# thermokoppel.net
KiCad netlist of a schematic drawn in Altium Designer
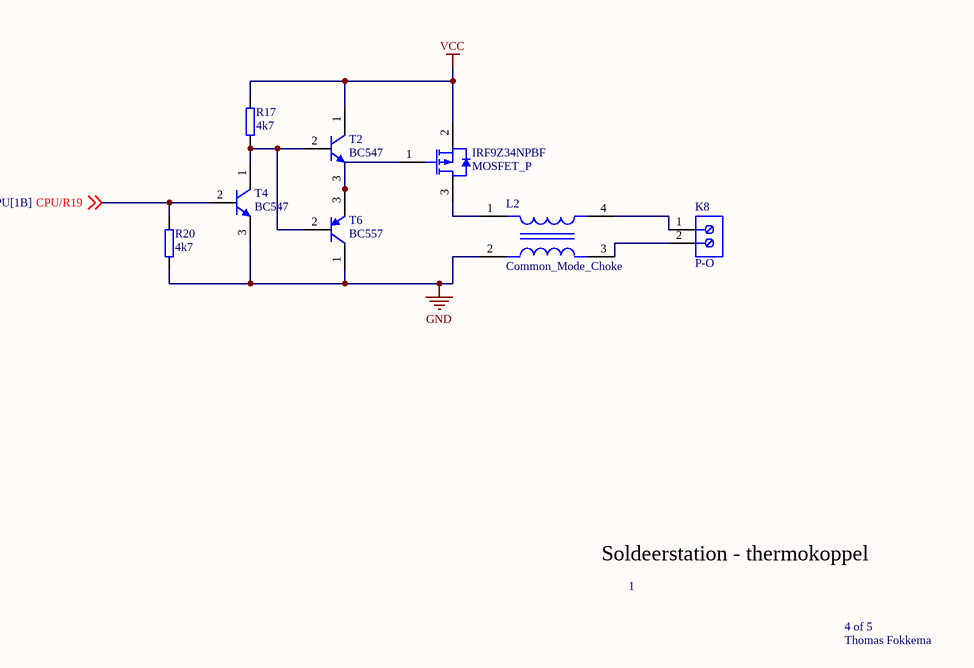
[diagram p0: thermokoppel.SchDoc]

(export (version "E")
  (design (tool "Eeschema 10.0.6"))
  (components
    (comp (ref "IRF9Z34NPBF")
      (value "MOSFET_P")
      (footprint "TO_252")
      (fields (field (name "MANUFACTURER") "Fairchild Semiconductor"))
      (libsource (lib "Soldeerstation_Final (1)") (part "MOSFET_P"))
    )
    (comp (ref "K8")
      (value "P-O")
      (footprint "PHOE-1714955_V")
      (description "PC Terminal Block, Pitch 6.35 mm, 1 x 2 Position, Height 21.5 mm, Tail Lenght 5.1 mm, RoHS, Bulk")
      (fields (field (name "MANUFACTURER") "Phoenix Contact"))
      (libsource (lib "Soldeerstation_Final") (part "CMP-2000-05797-1"))
    )
    (comp (ref "L2")
      (value "Common_Mode_Choke")
      (footprint "2545")
      (libsource (lib "Soldeerstation_Final (1)") (part "Common_Mode_Choke"))
    )
    (comp (ref "R17")
      (value "4k7")
      (footprint "R_0805_M")
      (fields (field (name "MANUFACTURER") "Vishay Dale") (field (name "PART NUMBER") "CRCW08050000Z0EA"))
      (libsource (lib "Soldeerstation_Final (1)") (part "Resistor"))
    )
    (comp (ref "R20")
      (value "4k7")
      (footprint "R_0805_M")
      (fields (field (name "MANUFACTURER") "Vishay Dale") (field (name "PART NUMBER") "CRCW08050000Z0EA"))
      (libsource (lib "Soldeerstation_Final (1)") (part "Resistor"))
    )
    (comp (ref "T2")
      (value "BC547")
      (footprint "SOT_23")
      (fields (field (name "MANUFACTURER") "On Semiconductor") (field (name "PARTNUMBER") "BC547C"))
      (libsource (lib "Soldeerstation_Final (1)") (part "Transistor_NPN"))
    )
    (comp (ref "T4")
      (value "BC547")
      (footprint "SOT_23")
      (fields (field (name "MANUFACTURER") "On Semiconductor") (field (name "PARTNUMBER") "BC547C"))
      (libsource (lib "Soldeerstation_Final (1)") (part "Transistor_NPN"))
    )
    (comp (ref "T6")
      (value "BC557")
      (footprint "SOT_23")
      (fields (field (name "MANUFACTURER") "On Semiconductor") (field (name "PARTNUMBER") "BC557C"))
      (libsource (lib "Soldeerstation_Final (1)") (part "Transistor_PNP"))
    )
  )
  (nets
    (net (code "1") (name "CPU{slash}R19") (class "Default")
      (node (ref "R20") (pin "2") (pinfunction "2_2") (pintype "passive"))
      (node (ref "T4") (pin "2") (pinfunction "B_2") (pintype "passive"))
    )
    (net (code "2") (name "GND") (class "Default")
      (node (ref "L2") (pin "2") (pinfunction "2_2") (pintype "passive"))
      (node (ref "R20") (pin "1") (pinfunction "1_1") (pintype "passive"))
      (node (ref "T4") (pin "3") (pinfunction "E_3") (pintype "passive"))
      (node (ref "T6") (pin "1") (pinfunction "C_1") (pintype "passive"))
    )
    (net (code "3") (name "Net-(IRF9Z34NPBF-DRAIN)") (class "Default")
      (node (ref "IRF9Z34NPBF") (pin "3") (pinfunction "DRAIN_3") (pintype "passive"))
      (node (ref "L2") (pin "1") (pinfunction "1_1") (pintype "passive"))
    )
    (net (code "4") (name "Net-(IRF9Z34NPBF-GATE)") (class "Default")
      (node (ref "IRF9Z34NPBF") (pin "1") (pinfunction "GATE_1") (pintype "passive"))
      (node (ref "T2") (pin "3") (pinfunction "E_3") (pintype "passive"))
      (node (ref "T6") (pin "3") (pinfunction "E_3") (pintype "passive"))
    )
    (net (code "5") (name "Net-(K8-Pad1)") (class "Default")
      (node (ref "K8") (pin "1") (pinfunction "1_1") (pintype "passive"))
      (node (ref "L2") (pin "4") (pinfunction "4_4") (pintype "passive"))
    )
    (net (code "6") (name "Net-(K8-Pad2)") (class "Default")
      (node (ref "K8") (pin "2") (pinfunction "2_2") (pintype "passive"))
      (node (ref "L2") (pin "3") (pinfunction "3_3") (pintype "passive"))
    )
    (net (code "7") (name "Net-(T2-B)") (class "Default")
      (node (ref "R17") (pin "1") (pinfunction "1_1") (pintype "passive"))
      (node (ref "T2") (pin "2") (pinfunction "B_2") (pintype "passive"))
      (node (ref "T4") (pin "1") (pinfunction "C_1") (pintype "passive"))
      (node (ref "T6") (pin "2") (pinfunction "B_2") (pintype "passive"))
    )
    (net (code "8") (name "VCC") (class "Default")
      (node (ref "IRF9Z34NPBF") (pin "2") (pinfunction "SOURCE_2") (pintype "passive"))
      (node (ref "R17") (pin "2") (pinfunction "2_2") (pintype "passive"))
      (node (ref "T2") (pin "1") (pinfunction "C_1") (pintype "passive"))
    )
  )
)
